# Tiefenentladeschutz-ohneLed.net
KiCad netlist of a schematic drawn in EAGLE
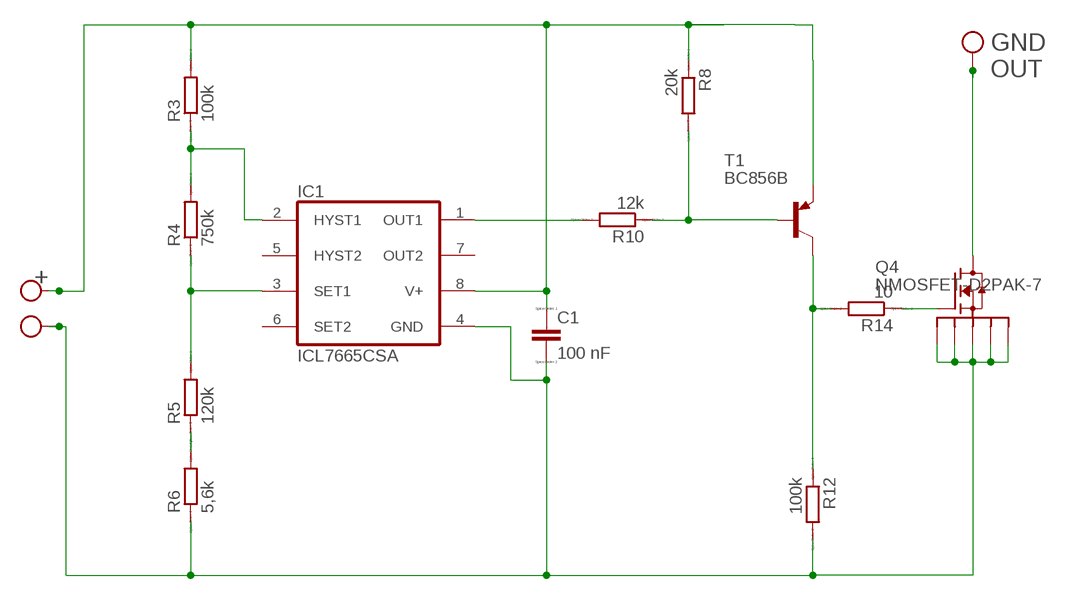
[diagram p0: schematic, sheet 1]

(export (version "E")
  (design (tool "Eeschema 10.0.6"))
  (components
    (comp (ref "C1")
      (value "100 nF")
      (footprint "eagle-import:C1206")
      (libsource (lib "eagle-import") (part "CC1206"))
    )
    (comp (ref "IC1")
      (value "ICL7665CSA")
      (footprint "eagle-import:SO08")
      (fields (field (name "MPN") "ICL7665CSA+"))
      (libsource (lib "eagle-import") (part "ICL7665CSA"))
    )
    (comp (ref "Q4")
      (value "NMOSFET-D2PAK-7")
      (footprint "eagle-import:H2PAK-6")
      (libsource (lib "eagle-import") (part "NMOSFET-D2PAK-7"))
    )
    (comp (ref "R3")
      (value "100k")
      (footprint "eagle-import:R1206")
      (libsource (lib "eagle-import") (part "RR1206"))
    )
    (comp (ref "R4")
      (value "750k")
      (footprint "eagle-import:R1206")
      (libsource (lib "eagle-import") (part "RR1206"))
    )
    (comp (ref "R5")
      (value "120k")
      (footprint "eagle-import:R1206")
      (libsource (lib "eagle-import") (part "RR1206"))
    )
    (comp (ref "R6")
      (value "5,6k")
      (footprint "eagle-import:R1206")
      (libsource (lib "eagle-import") (part "RR1206"))
    )
    (comp (ref "R8")
      (value "20k")
      (footprint "eagle-import:R1206")
      (libsource (lib "eagle-import") (part "RR1206"))
    )
    (comp (ref "R10")
      (value "12k")
      (footprint "eagle-import:R1206")
      (libsource (lib "eagle-import") (part "RR1206"))
    )
    (comp (ref "R12")
      (value "100k")
      (footprint "eagle-import:R1206")
      (libsource (lib "eagle-import") (part "RR1206"))
    )
    (comp (ref "R14")
      (value "10")
      (footprint "eagle-import:R1206")
      (libsource (lib "eagle-import") (part "RR1206"))
    )
    (comp (ref "T1")
      (value "BC856B")
      (footprint "eagle-import:SOT23-BEC")
      (libsource (lib "eagle-import") (part "-PNP-SOT23-BECBC856B"))
    )
    (comp (ref "U$4")
      (value "PIN2.54")
      (footprint "eagle-import:PIN")
      (libsource (lib "eagle-import") (part "PIN2.54"))
    )
    (comp (ref "U$6")
      (value "PIN1.27")
      (footprint "eagle-import:PIN-1.27")
      (libsource (lib "eagle-import") (part "PIN1.27"))
    )
    (comp (ref "U$7")
      (value "PIN1.27")
      (footprint "eagle-import:PIN-1.27")
      (libsource (lib "eagle-import") (part "PIN1.27"))
    )
  )
  (nets
    (net (code "1") (name "Net-(IC1-GND)") (class "Default")
      (node (ref "C1") (pin "2") (pinfunction "2_2") (pintype "passive"))
      (node (ref "IC1") (pin "4") (pinfunction "GND_4") (pintype "power_in"))
      (node (ref "Q4") (pin "S1") (pinfunction "S1_S1") (pintype "passive"))
      (node (ref "Q4") (pin "S2") (pinfunction "S2_S2") (pintype "passive"))
      (node (ref "Q4") (pin "S3") (pinfunction "S3_S3") (pintype "passive"))
      (node (ref "Q4") (pin "S4") (pinfunction "S4_S4") (pintype "passive"))
      (node (ref "Q4") (pin "S5") (pinfunction "S5_S5") (pintype "passive"))
      (node (ref "R12") (pin "2") (pinfunction "2_2") (pintype "passive"))
      (node (ref "R6") (pin "1") (pinfunction "1_1") (pintype "passive"))
      (node (ref "U$6") (pin "P$1") (pinfunction "P$1_P$1") (pintype "bidirectional"))
    )
    (net (code "2") (name "Net-(IC1-HYST1)") (class "Default")
      (node (ref "IC1") (pin "2") (pinfunction "HYST1_2") (pintype "input"))
      (node (ref "R3") (pin "1") (pinfunction "1_1") (pintype "passive"))
      (node (ref "R4") (pin "2") (pinfunction "2_2") (pintype "passive"))
    )
    (net (code "3") (name "Net-(IC1-OUT1)") (class "Default")
      (node (ref "IC1") (pin "1") (pinfunction "OUT1_1") (pintype "output"))
      (node (ref "R10") (pin "2") (pinfunction "2_2") (pintype "passive"))
    )
    (net (code "4") (name "Net-(IC1-SET1)") (class "Default")
      (node (ref "IC1") (pin "3") (pinfunction "SET1_3") (pintype "input"))
      (node (ref "R4") (pin "1") (pinfunction "1_1") (pintype "passive"))
      (node (ref "R5") (pin "2") (pinfunction "2_2") (pintype "passive"))
    )
    (net (code "5") (name "Net-(IC1-V+)") (class "Default")
      (node (ref "C1") (pin "1") (pinfunction "1_1") (pintype "passive"))
      (node (ref "IC1") (pin "8") (pinfunction "V+_8") (pintype "power_in"))
      (node (ref "R3") (pin "2") (pinfunction "2_2") (pintype "passive"))
      (node (ref "R8") (pin "1") (pinfunction "1_1") (pintype "passive"))
      (node (ref "T1") (pin "E") (pinfunction "E_E") (pintype "passive"))
      (node (ref "U$4") (pin "P$1") (pinfunction "P$1_P$1") (pintype "bidirectional"))
    )
    (net (code "6") (name "Net-(Q4-PadD)") (class "Default")
      (node (ref "Q4") (pin "D") (pinfunction "D_D") (pintype "passive"))
      (node (ref "U$7") (pin "P$1") (pinfunction "P$1_P$1") (pintype "bidirectional"))
    )
    (net (code "7") (name "Net-(Q4-PadG)") (class "Default")
      (node (ref "Q4") (pin "G") (pinfunction "G_G") (pintype "passive"))
      (node (ref "R14") (pin "1") (pinfunction "1_1") (pintype "passive"))
    )
    (net (code "8") (name "Net-(R5-Pad1)") (class "Default")
      (node (ref "R5") (pin "1") (pinfunction "1_1") (pintype "passive"))
      (node (ref "R6") (pin "2") (pinfunction "2_2") (pintype "passive"))
    )
    (net (code "9") (name "Net-(R10-Pad1)") (class "Default")
      (node (ref "R10") (pin "1") (pinfunction "1_1") (pintype "passive"))
      (node (ref "R8") (pin "2") (pinfunction "2_2") (pintype "passive"))
      (node (ref "T1") (pin "B") (pinfunction "B_B") (pintype "passive"))
    )
    (net (code "10") (name "Net-(R12-Pad1)") (class "Default")
      (node (ref "R12") (pin "1") (pinfunction "1_1") (pintype "passive"))
      (node (ref "R14") (pin "2") (pinfunction "2_2") (pintype "passive"))
      (node (ref "T1") (pin "C") (pinfunction "C_C") (pintype "passive"))
    )
    (net (code "11") (name "unconnected-(IC1-HYST2-Pad5)") (class "Default")
      (node (ref "IC1") (pin "5") (pinfunction "HYST2_5") (pintype "input"))
    )
    (net (code "12") (name "unconnected-(IC1-OUT2-Pad7)") (class "Default")
      (node (ref "IC1") (pin "7") (pinfunction "OUT2_7") (pintype "output"))
    )
    (net (code "13") (name "unconnected-(IC1-SET2-Pad6)") (class "Default")
      (node (ref "IC1") (pin "6") (pinfunction "SET2_6") (pintype "input"))
    )
  )
)
